# ProPrj_USB_Connector_2025-09-04.net
KiCad netlist of a schematic drawn in EasyEDA Pro
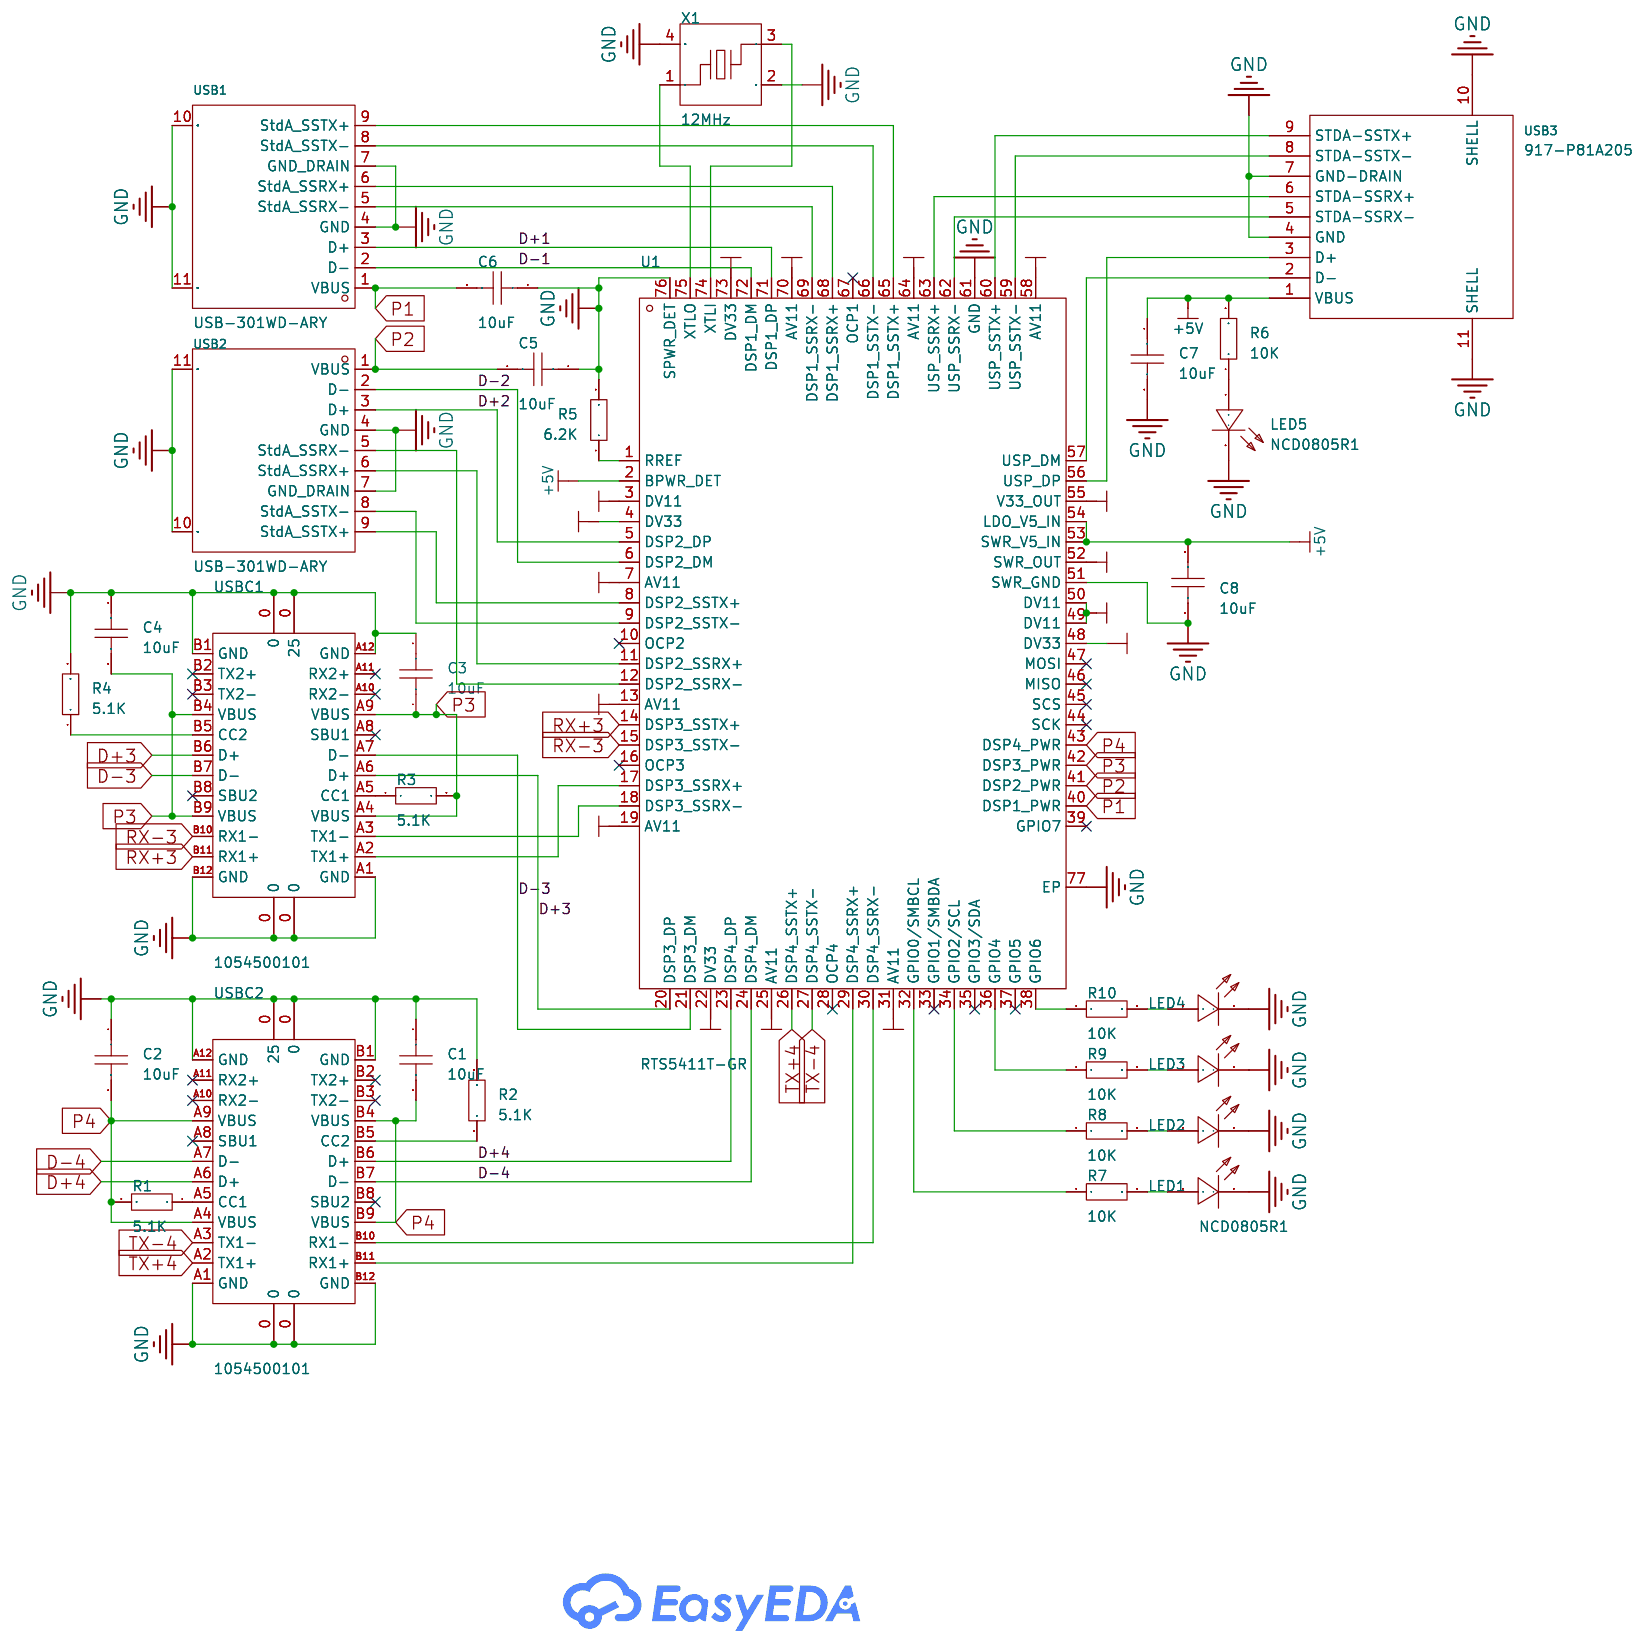
[diagram p0: schematic sheet]

(export (version "E")
  (design (tool "Eeschema 10.0.6"))
  (components
    (comp (ref "C1")
      (value "10uF")
      (footprint "easyedapro:C0603")
      (libsource (lib "easyedapro") (part "CAP"))
    )
    (comp (ref "C2")
      (value "10uF")
      (footprint "easyedapro:C0603")
      (libsource (lib "easyedapro") (part "CAP"))
    )
    (comp (ref "C3")
      (value "10uF")
      (footprint "easyedapro:C0603")
      (libsource (lib "easyedapro") (part "CAP"))
    )
    (comp (ref "C4")
      (value "10uF")
      (footprint "easyedapro:C0603")
      (libsource (lib "easyedapro") (part "CAP"))
    )
    (comp (ref "C5")
      (value "10uF")
      (footprint "easyedapro:C0603")
      (libsource (lib "easyedapro") (part "CAP"))
    )
    (comp (ref "C6")
      (value "10uF")
      (footprint "easyedapro:C0603")
      (libsource (lib "easyedapro") (part "CAP"))
    )
    (comp (ref "C7")
      (value "10uF")
      (footprint "easyedapro:C0603")
      (libsource (lib "easyedapro") (part "CAP"))
    )
    (comp (ref "C8")
      (value "10uF")
      (footprint "easyedapro:C0603")
      (libsource (lib "easyedapro") (part "CAP"))
    )
    (comp (ref "LED1")
      (value "NCD0805R1")
      (footprint "easyedapro:LED0805-R-RD")
      (fields (field (name "Manufacturer") "国星光电"))
      (libsource (lib "easyedapro") (part "FC-2012HRK-620D"))
    )
    (comp (ref "LED2")
      (value "NCD0805R1")
      (footprint "easyedapro:LED0805-R-RD")
      (fields (field (name "Manufacturer") "国星光电"))
      (libsource (lib "easyedapro") (part "FC-2012HRK-620D"))
    )
    (comp (ref "LED3")
      (value "NCD0805R1")
      (footprint "easyedapro:LED0805-R-RD")
      (fields (field (name "Manufacturer") "国星光电"))
      (libsource (lib "easyedapro") (part "FC-2012HRK-620D"))
    )
    (comp (ref "LED4")
      (value "NCD0805R1")
      (footprint "easyedapro:LED0805-R-RD")
      (fields (field (name "Manufacturer") "国星光电"))
      (libsource (lib "easyedapro") (part "FC-2012HRK-620D"))
    )
    (comp (ref "LED5")
      (value "NCD0805R1")
      (footprint "easyedapro:LED0805-R-RD")
      (fields (field (name "Manufacturer") "国星光电"))
      (libsource (lib "easyedapro") (part "FC-2012HRK-620D"))
    )
    (comp (ref "R1")
      (value "5.1K")
      (footprint "easyedapro:R0603")
      (libsource (lib "easyedapro") (part "Res"))
    )
    (comp (ref "R2")
      (value "5.1K")
      (footprint "easyedapro:R0603")
      (libsource (lib "easyedapro") (part "Res"))
    )
    (comp (ref "R3")
      (value "5.1K")
      (footprint "easyedapro:R0603")
      (libsource (lib "easyedapro") (part "Res"))
    )
    (comp (ref "R4")
      (value "5.1K")
      (footprint "easyedapro:R0603")
      (libsource (lib "easyedapro") (part "Res"))
    )
    (comp (ref "R5")
      (value "6.2K")
      (footprint "easyedapro:R0603")
      (libsource (lib "easyedapro") (part "Res"))
    )
    (comp (ref "R6") (value "10K") (footprint "easyedapro:R0603") (libsource (lib "easyedapro") (part "Res")))
    (comp (ref "R7") (value "10K") (footprint "easyedapro:R0603") (libsource (lib "easyedapro") (part "Res")))
    (comp (ref "R8") (value "10K") (footprint "easyedapro:R0603") (libsource (lib "easyedapro") (part "Res")))
    (comp (ref "R9") (value "10K") (footprint "easyedapro:R0603") (libsource (lib "easyedapro") (part "Res")))
    (comp (ref "R10")
      (value "10K")
      (footprint "easyedapro:R0603")
      (libsource (lib "easyedapro") (part "Res"))
    )
    (comp (ref "U1")
      (value "RTS5411T-GR")
      (footprint "easyedapro:QFN-76_L9.0-W9.0-P0.40-BL-EP5.4")
      (fields (field (name "Manufacturer") "REALTEK(瑞昱)"))
      (libsource (lib "easyedapro") (part "RTS5411T-GR"))
    )
    (comp (ref "USB1")
      (value "USB-301WD-ARY")
      (footprint "easyedapro:USB-TH_XUNPU_USB-301WD-ARY")
      (fields (field (name "Manufacturer") "XUNPU(讯普)"))
      (libsource (lib "easyedapro") (part "USB-301WD-ARY"))
    )
    (comp (ref "USB2")
      (value "USB-301WD-ARY")
      (footprint "easyedapro:USB-TH_XUNPU_USB-301WD-ARY")
      (fields (field (name "Manufacturer") "XUNPU(讯普)"))
      (libsource (lib "easyedapro") (part "USB-301WD-ARY"))
    )
    (comp (ref "USB3")
      (value "917-P81A205CS60202")
      (footprint "easyedapro:USB-3.0-SMD_CU3M002_USBA-M")
      (fields (field (name "Manufacturer") "精拓金"))
      (libsource (lib "easyedapro") (part "CU3M002_USB A/M 3.0 SMT L=1.9 K"))
    )
    (comp (ref "USBC1")
      (value "1054500101")
      (footprint "easyedapro:USB-C-SMD_TYPE-C-USB-18")
      (fields (field (name "Manufacturer") "MOLEX"))
      (libsource (lib "easyedapro") (part "105450-0101"))
    )
    (comp (ref "USBC2")
      (value "1054500101")
      (footprint "easyedapro:USB-C-SMD_TYPE-C-USB-18")
      (fields (field (name "Manufacturer") "MOLEX"))
      (libsource (lib "easyedapro") (part "105450-0101"))
    )
    (comp (ref "X1")
      (value "12MHz")
      (footprint "easyedapro:CRYSTAL-SMD_4P-L3.2-W2.5-BL-1")
      (fields
        (field (name "Manufacturer Part") "XL2EL89COI-111YLC-12M")
        (field (name "Manufacturer") "YXC(扬兴晶振)")
      )
      (libsource (lib "easyedapro") (part "XL2EL89COI-111YLC-12M"))
    )
  )
  (nets
    (net (code "1") (name "+1V1") (class "Default")
      (node (ref "U1") (pin "13") (pinfunction "AV11_13") (pintype "unspecified"))
      (node (ref "U1") (pin "19") (pinfunction "AV11_19") (pintype "unspecified"))
      (node (ref "U1") (pin "25") (pinfunction "AV11_25") (pintype "unspecified"))
      (node (ref "U1") (pin "3") (pinfunction "DV11_3") (pintype "unspecified"))
      (node (ref "U1") (pin "31") (pinfunction "AV11_31") (pintype "unspecified"))
      (node (ref "U1") (pin "49") (pinfunction "DV11_49") (pintype "unspecified"))
      (node (ref "U1") (pin "50") (pinfunction "DV11_50") (pintype "unspecified"))
      (node (ref "U1") (pin "52") (pinfunction "SWR_OUT_52") (pintype "unspecified"))
      (node (ref "U1") (pin "58") (pinfunction "AV11_58") (pintype "unspecified"))
      (node (ref "U1") (pin "64") (pinfunction "AV11_64") (pintype "unspecified"))
      (node (ref "U1") (pin "7") (pinfunction "AV11_7") (pintype "unspecified"))
      (node (ref "U1") (pin "70") (pinfunction "AV11_70") (pintype "unspecified"))
    )
    (net (code "2") (name "+3V3") (class "Default")
      (node (ref "U1") (pin "22") (pinfunction "DV33_22") (pintype "unspecified"))
      (node (ref "U1") (pin "4") (pinfunction "DV33_4") (pintype "unspecified"))
      (node (ref "U1") (pin "48") (pinfunction "DV33_48") (pintype "unspecified"))
      (node (ref "U1") (pin "55") (pinfunction "V33_OUT_55") (pintype "unspecified"))
      (node (ref "U1") (pin "73") (pinfunction "DV33_73") (pintype "unspecified"))
    )
    (net (code "3") (name "+5V") (class "Default")
      (node (ref "C7") (pin "1") (pinfunction "1_1") (pintype "input"))
      (node (ref "C8") (pin "2") (pinfunction "2_2") (pintype "input"))
      (node (ref "R6") (pin "2") (pinfunction "2_2") (pintype "input"))
      (node (ref "U1") (pin "2") (pinfunction "BPWR_DET_2") (pintype "unspecified"))
      (node (ref "U1") (pin "53") (pinfunction "SWR_V5_IN_53") (pintype "unspecified"))
      (node (ref "U1") (pin "54") (pinfunction "LDO_V5_IN_54") (pintype "unspecified"))
      (node (ref "USB3") (pin "1") (pinfunction "VBUS_1") (pintype "input"))
    )
    (net (code "4") (name "/D+1") (class "Default")
      (node (ref "U1") (pin "71") (pinfunction "DSP1_DP_71") (pintype "unspecified"))
      (node (ref "USB1") (pin "3") (pinfunction "D+_3") (pintype "input"))
    )
    (net (code "5") (name "/D+2") (class "Default")
      (node (ref "U1") (pin "5") (pinfunction "DSP2_DP_5") (pintype "unspecified"))
      (node (ref "USB2") (pin "3") (pinfunction "D+_3") (pintype "input"))
    )
    (net (code "6") (name "/D-1") (class "Default")
      (node (ref "U1") (pin "72") (pinfunction "DSP1_DM_72") (pintype "unspecified"))
      (node (ref "USB1") (pin "2") (pinfunction "D-_2") (pintype "input"))
    )
    (net (code "7") (name "/D-2") (class "Default")
      (node (ref "U1") (pin "6") (pinfunction "DSP2_DM_6") (pintype "unspecified"))
      (node (ref "USB2") (pin "2") (pinfunction "D-_2") (pintype "input"))
    )
    (net (code "8") (name "D+3") (class "Default")
      (node (ref "U1") (pin "20") (pinfunction "DSP3_DP_20") (pintype "unspecified"))
      (node (ref "USBC1") (pin "A6") (pinfunction "D+_A6") (pintype "unspecified"))
      (node (ref "USBC1") (pin "B6") (pinfunction "D+_B6") (pintype "unspecified"))
    )
    (net (code "9") (name "D+4") (class "Default")
      (node (ref "U1") (pin "23") (pinfunction "DSP4_DP_23") (pintype "unspecified"))
      (node (ref "USBC2") (pin "A6") (pinfunction "D+_A6") (pintype "unspecified"))
      (node (ref "USBC2") (pin "B6") (pinfunction "D+_B6") (pintype "unspecified"))
    )
    (net (code "10") (name "D-3") (class "Default")
      (node (ref "U1") (pin "21") (pinfunction "DSP3_DM_21") (pintype "unspecified"))
      (node (ref "USBC1") (pin "A7") (pinfunction "D-_A7") (pintype "unspecified"))
      (node (ref "USBC1") (pin "B7") (pinfunction "D-_B7") (pintype "unspecified"))
    )
    (net (code "11") (name "D-4") (class "Default")
      (node (ref "U1") (pin "24") (pinfunction "DSP4_DM_24") (pintype "unspecified"))
      (node (ref "USBC2") (pin "A7") (pinfunction "D-_A7") (pintype "unspecified"))
      (node (ref "USBC2") (pin "B7") (pinfunction "D-_B7") (pintype "unspecified"))
    )
    (net (code "12") (name "GND") (class "Default")
      (node (ref "C1") (pin "1") (pinfunction "1_1") (pintype "input"))
      (node (ref "C2") (pin "1") (pinfunction "1_1") (pintype "input"))
      (node (ref "C3") (pin "2") (pinfunction "2_2") (pintype "input"))
      (node (ref "C4") (pin "1") (pinfunction "1_1") (pintype "input"))
      (node (ref "C5") (pin "1") (pinfunction "1_1") (pintype "input"))
      (node (ref "C6") (pin "1") (pinfunction "1_1") (pintype "input"))
      (node (ref "C7") (pin "2") (pinfunction "2_2") (pintype "input"))
      (node (ref "C8") (pin "1") (pinfunction "1_1") (pintype "input"))
      (node (ref "LED1") (pin "2") (pinfunction "-_2") (pintype "unspecified"))
      (node (ref "LED2") (pin "2") (pinfunction "-_2") (pintype "unspecified"))
      (node (ref "LED3") (pin "2") (pinfunction "-_2") (pintype "unspecified"))
      (node (ref "LED4") (pin "2") (pinfunction "-_2") (pintype "unspecified"))
      (node (ref "LED5") (pin "2") (pinfunction "-_2") (pintype "unspecified"))
      (node (ref "R2") (pin "2") (pinfunction "2_2") (pintype "input"))
      (node (ref "R4") (pin "2") (pinfunction "2_2") (pintype "input"))
      (node (ref "R5") (pin "2") (pinfunction "2_2") (pintype "input"))
      (node (ref "U1") (pin "51") (pinfunction "SWR_GND_51") (pintype "unspecified"))
      (node (ref "U1") (pin "61") (pinfunction "GND_61") (pintype "unspecified"))
      (node (ref "U1") (pin "76") (pinfunction "SPWR_DET_76") (pintype "unspecified"))
      (node (ref "U1") (pin "77") (pinfunction "EP_77") (pintype "unspecified"))
      (node (ref "USB1") (pin "10") (pinfunction "SHIELD_10") (pintype "input"))
      (node (ref "USB1") (pin "11") (pinfunction "SHIELD_11") (pintype "input"))
      (node (ref "USB1") (pin "4") (pinfunction "GND_4") (pintype "input"))
      (node (ref "USB1") (pin "7") (pinfunction "GND_DRAIN_7") (pintype "input"))
      (node (ref "USB2") (pin "10") (pinfunction "SHIELD_10") (pintype "input"))
      (node (ref "USB2") (pin "11") (pinfunction "SHIELD_11") (pintype "input"))
      (node (ref "USB2") (pin "4") (pinfunction "GND_4") (pintype "input"))
      (node (ref "USB2") (pin "7") (pinfunction "GND_DRAIN_7") (pintype "input"))
      (node (ref "USB3") (pin "10") (pinfunction "SHELL_10") (pintype "input"))
      (node (ref "USB3") (pin "11") (pinfunction "SHELL_11") (pintype "input"))
      (node (ref "USB3") (pin "4") (pinfunction "GND_4") (pintype "input"))
      (node (ref "USB3") (pin "7") (pinfunction "GND-DRAIN_7") (pintype "input"))
      (node (ref "USBC1") (pin "0") (pinfunction "0_0") (pintype "unspecified"))
      (node (ref "USBC1") (pin "A1") (pinfunction "GND_A1") (pintype "unspecified"))
      (node (ref "USBC1") (pin "A12") (pinfunction "GND_A12") (pintype "unspecified"))
      (node (ref "USBC1") (pin "B1") (pinfunction "GND_B1") (pintype "unspecified"))
      (node (ref "USBC1") (pin "B12") (pinfunction "GND_B12") (pintype "unspecified"))
      (node (ref "USBC2") (pin "0") (pinfunction "25_0") (pintype "unspecified"))
      (node (ref "USBC2") (pin "A1") (pinfunction "GND_A1") (pintype "unspecified"))
      (node (ref "USBC2") (pin "A12") (pinfunction "GND_A12") (pintype "unspecified"))
      (node (ref "USBC2") (pin "B1") (pinfunction "GND_B1") (pintype "unspecified"))
      (node (ref "USBC2") (pin "B12") (pinfunction "GND_B12") (pintype "unspecified"))
      (node (ref "X1") (pin "2") (pinfunction "GND_2") (pintype "input"))
      (node (ref "X1") (pin "4") (pinfunction "GND_4") (pintype "input"))
    )
    (net (code "13") (name "Net-(LED1-+)") (class "Default")
      (node (ref "LED1") (pin "1") (pinfunction "+_1") (pintype "unspecified"))
      (node (ref "R7") (pin "2") (pinfunction "2_2") (pintype "input"))
    )
    (net (code "14") (name "Net-(LED2-+)") (class "Default")
      (node (ref "LED2") (pin "1") (pinfunction "+_1") (pintype "unspecified"))
      (node (ref "R8") (pin "2") (pinfunction "2_2") (pintype "input"))
    )
    (net (code "15") (name "Net-(LED3-+)") (class "Default")
      (node (ref "LED3") (pin "1") (pinfunction "+_1") (pintype "unspecified"))
      (node (ref "R9") (pin "2") (pinfunction "2_2") (pintype "input"))
    )
    (net (code "16") (name "Net-(LED4-+)") (class "Default")
      (node (ref "LED4") (pin "1") (pinfunction "+_1") (pintype "unspecified"))
      (node (ref "R10") (pin "2") (pinfunction "2_2") (pintype "input"))
    )
    (net (code "17") (name "Net-(LED5-+)") (class "Default")
      (node (ref "LED5") (pin "1") (pinfunction "+_1") (pintype "unspecified"))
      (node (ref "R6") (pin "1") (pinfunction "1_1") (pintype "input"))
    )
    (net (code "18") (name "Net-(U1-DSP1_SSRX+)") (class "Default")
      (node (ref "U1") (pin "68") (pinfunction "DSP1_SSRX+_68") (pintype "unspecified"))
      (node (ref "USB1") (pin "6") (pinfunction "StdA_SSRX+_6") (pintype "input"))
    )
    (net (code "19") (name "Net-(U1-DSP1_SSRX-)") (class "Default")
      (node (ref "U1") (pin "69") (pinfunction "DSP1_SSRX-_69") (pintype "unspecified"))
      (node (ref "USB1") (pin "5") (pinfunction "StdA_SSRX-_5") (pintype "input"))
    )
    (net (code "20") (name "Net-(U1-DSP1_SSTX+)") (class "Default")
      (node (ref "U1") (pin "65") (pinfunction "DSP1_SSTX+_65") (pintype "unspecified"))
      (node (ref "USB1") (pin "9") (pinfunction "StdA_SSTX+_9") (pintype "input"))
    )
    (net (code "21") (name "Net-(U1-DSP1_SSTX-)") (class "Default")
      (node (ref "U1") (pin "66") (pinfunction "DSP1_SSTX-_66") (pintype "unspecified"))
      (node (ref "USB1") (pin "8") (pinfunction "StdA_SSTX-_8") (pintype "input"))
    )
    (net (code "22") (name "Net-(U1-DSP2_SSRX+)") (class "Default")
      (node (ref "U1") (pin "11") (pinfunction "DSP2_SSRX+_11") (pintype "unspecified"))
      (node (ref "USB2") (pin "6") (pinfunction "StdA_SSRX+_6") (pintype "input"))
    )
    (net (code "23") (name "Net-(U1-DSP2_SSRX-)") (class "Default")
      (node (ref "U1") (pin "12") (pinfunction "DSP2_SSRX-_12") (pintype "unspecified"))
      (node (ref "USB2") (pin "5") (pinfunction "StdA_SSRX-_5") (pintype "input"))
    )
    (net (code "24") (name "Net-(U1-DSP2_SSTX+)") (class "Default")
      (node (ref "U1") (pin "8") (pinfunction "DSP2_SSTX+_8") (pintype "unspecified"))
      (node (ref "USB2") (pin "9") (pinfunction "StdA_SSTX+_9") (pintype "input"))
    )
    (net (code "25") (name "Net-(U1-DSP2_SSTX-)") (class "Default")
      (node (ref "U1") (pin "9") (pinfunction "DSP2_SSTX-_9") (pintype "unspecified"))
      (node (ref "USB2") (pin "8") (pinfunction "StdA_SSTX-_8") (pintype "input"))
    )
    (net (code "26") (name "Net-(U1-DSP3_SSRX+)") (class "Default")
      (node (ref "U1") (pin "17") (pinfunction "DSP3_SSRX+_17") (pintype "unspecified"))
      (node (ref "USBC1") (pin "A2") (pinfunction "TX1+_A2") (pintype "unspecified"))
    )
    (net (code "27") (name "Net-(U1-DSP3_SSRX-)") (class "Default")
      (node (ref "U1") (pin "18") (pinfunction "DSP3_SSRX-_18") (pintype "unspecified"))
      (node (ref "USBC1") (pin "A3") (pinfunction "TX1-_A3") (pintype "unspecified"))
    )
    (net (code "28") (name "Net-(U1-DSP4_SSRX+)") (class "Default")
      (node (ref "U1") (pin "29") (pinfunction "DSP4_SSRX+_29") (pintype "unspecified"))
      (node (ref "USBC2") (pin "B11") (pinfunction "RX1+_B11") (pintype "unspecified"))
    )
    (net (code "29") (name "Net-(U1-DSP4_SSRX-)") (class "Default")
      (node (ref "U1") (pin "30") (pinfunction "DSP4_SSRX-_30") (pintype "unspecified"))
      (node (ref "USBC2") (pin "B10") (pinfunction "RX1-_B10") (pintype "unspecified"))
    )
    (net (code "30") (name "Net-(U1-GPIO0{slash}SMBCL)") (class "Default")
      (node (ref "R7") (pin "1") (pinfunction "1_1") (pintype "input"))
      (node (ref "U1") (pin "32") (pinfunction "GPIO0/SMBCL_32") (pintype "unspecified"))
    )
    (net (code "31") (name "Net-(U1-GPIO2{slash}SCL)") (class "Default")
      (node (ref "R8") (pin "1") (pinfunction "1_1") (pintype "input"))
      (node (ref "U1") (pin "34") (pinfunction "GPIO2/SCL_34") (pintype "unspecified"))
    )
    (net (code "32") (name "Net-(U1-GPIO4)") (class "Default")
      (node (ref "R9") (pin "1") (pinfunction "1_1") (pintype "input"))
      (node (ref "U1") (pin "36") (pinfunction "GPIO4_36") (pintype "unspecified"))
    )
    (net (code "33") (name "Net-(U1-GPIO6)") (class "Default")
      (node (ref "R10") (pin "1") (pinfunction "1_1") (pintype "input"))
      (node (ref "U1") (pin "38") (pinfunction "GPIO6_38") (pintype "unspecified"))
    )
    (net (code "34") (name "Net-(U1-RREF)") (class "Default")
      (node (ref "R5") (pin "1") (pinfunction "1_1") (pintype "input"))
      (node (ref "U1") (pin "1") (pinfunction "RREF_1") (pintype "unspecified"))
    )
    (net (code "35") (name "Net-(U1-USP_DM)") (class "Default")
      (node (ref "U1") (pin "57") (pinfunction "USP_DM_57") (pintype "unspecified"))
      (node (ref "USB3") (pin "2") (pinfunction "D-_2") (pintype "input"))
    )
    (net (code "36") (name "Net-(U1-USP_DP)") (class "Default")
      (node (ref "U1") (pin "56") (pinfunction "USP_DP_56") (pintype "unspecified"))
      (node (ref "USB3") (pin "3") (pinfunction "D+_3") (pintype "input"))
    )
    (net (code "37") (name "Net-(U1-USP_SSRX+)") (class "Default")
      (node (ref "U1") (pin "63") (pinfunction "USP_SSRX+_63") (pintype "unspecified"))
      (node (ref "USB3") (pin "6") (pinfunction "STDA-SSRX+_6") (pintype "input"))
    )
    (net (code "38") (name "Net-(U1-USP_SSRX-)") (class "Default")
      (node (ref "U1") (pin "62") (pinfunction "USP_SSRX-_62") (pintype "unspecified"))
      (node (ref "USB3") (pin "5") (pinfunction "STDA-SSRX-_5") (pintype "input"))
    )
    (net (code "39") (name "Net-(U1-USP_SSTX+)") (class "Default")
      (node (ref "U1") (pin "60") (pinfunction "USP_SSTX+_60") (pintype "unspecified"))
      (node (ref "USB3") (pin "9") (pinfunction "STDA-SSTX+_9") (pintype "input"))
    )
    (net (code "40") (name "Net-(U1-USP_SSTX-)") (class "Default")
      (node (ref "U1") (pin "59") (pinfunction "USP_SSTX-_59") (pintype "unspecified"))
      (node (ref "USB3") (pin "8") (pinfunction "STDA-SSTX-_8") (pintype "input"))
    )
    (net (code "41") (name "Net-(U1-XTLI)") (class "Default")
      (node (ref "U1") (pin "74") (pinfunction "XTLI_74") (pintype "unspecified"))
      (node (ref "X1") (pin "3") (pinfunction "3_3") (pintype "input"))
    )
    (net (code "42") (name "Net-(U1-XTLO)") (class "Default")
      (node (ref "U1") (pin "75") (pinfunction "XTLO_75") (pintype "unspecified"))
      (node (ref "X1") (pin "1") (pinfunction "1_1") (pintype "input"))
    )
    (net (code "43") (name "Net-(USBC1-CC1)") (class "Default")
      (node (ref "R3") (pin "1") (pinfunction "1_1") (pintype "input"))
      (node (ref "USBC1") (pin "A5") (pinfunction "CC1_A5") (pintype "unspecified"))
    )
    (net (code "44") (name "Net-(USBC1-CC2)") (class "Default")
      (node (ref "R4") (pin "1") (pinfunction "1_1") (pintype "input"))
      (node (ref "USBC1") (pin "B5") (pinfunction "CC2_B5") (pintype "unspecified"))
    )
    (net (code "45") (name "Net-(USBC2-CC1)") (class "Default")
      (node (ref "R1") (pin "1") (pinfunction "1_1") (pintype "input"))
      (node (ref "USBC2") (pin "A5") (pinfunction "CC1_A5") (pintype "unspecified"))
    )
    (net (code "46") (name "Net-(USBC2-CC2)") (class "Default")
      (node (ref "R2") (pin "1") (pinfunction "1_1") (pintype "input"))
      (node (ref "USBC2") (pin "B5") (pinfunction "CC2_B5") (pintype "unspecified"))
    )
    (net (code "47") (name "P1") (class "Default")
      (node (ref "C6") (pin "2") (pinfunction "2_2") (pintype "input"))
      (node (ref "U1") (pin "40") (pinfunction "DSP1_PWR_40") (pintype "unspecified"))
      (node (ref "USB1") (pin "1") (pinfunction "VBUS_1") (pintype "input"))
    )
    (net (code "48") (name "P2") (class "Default")
      (node (ref "C5") (pin "2") (pinfunction "2_2") (pintype "input"))
      (node (ref "U1") (pin "41") (pinfunction "DSP2_PWR_41") (pintype "unspecified"))
      (node (ref "USB2") (pin "1") (pinfunction "VBUS_1") (pintype "input"))
    )
    (net (code "49") (name "P3") (class "Default")
      (node (ref "C3") (pin "1") (pinfunction "1_1") (pintype "input"))
      (node (ref "C4") (pin "2") (pinfunction "2_2") (pintype "input"))
      (node (ref "R3") (pin "2") (pinfunction "2_2") (pintype "input"))
      (node (ref "U1") (pin "42") (pinfunction "DSP3_PWR_42") (pintype "unspecified"))
      (node (ref "USBC1") (pin "A4") (pinfunction "VBUS_A4") (pintype "unspecified"))
      (node (ref "USBC1") (pin "A9") (pinfunction "VBUS_A9") (pintype "unspecified"))
      (node (ref "USBC1") (pin "B4") (pinfunction "VBUS_B4") (pintype "unspecified"))
      (node (ref "USBC1") (pin "B9") (pinfunction "VBUS_B9") (pintype "unspecified"))
    )
    (net (code "50") (name "P4") (class "Default")
      (node (ref "C1") (pin "2") (pinfunction "2_2") (pintype "input"))
      (node (ref "C2") (pin "2") (pinfunction "2_2") (pintype "input"))
      (node (ref "R1") (pin "2") (pinfunction "2_2") (pintype "input"))
      (node (ref "U1") (pin "43") (pinfunction "DSP4_PWR_43") (pintype "unspecified"))
      (node (ref "USBC2") (pin "A4") (pinfunction "VBUS_A4") (pintype "unspecified"))
      (node (ref "USBC2") (pin "A9") (pinfunction "VBUS_A9") (pintype "unspecified"))
      (node (ref "USBC2") (pin "B4") (pinfunction "VBUS_B4") (pintype "unspecified"))
      (node (ref "USBC2") (pin "B9") (pinfunction "VBUS_B9") (pintype "unspecified"))
    )
    (net (code "51") (name "RX+3") (class "Default")
      (node (ref "U1") (pin "14") (pinfunction "DSP3_SSTX+_14") (pintype "unspecified"))
      (node (ref "USBC1") (pin "B11") (pinfunction "RX1+_B11") (pintype "unspecified"))
    )
    (net (code "52") (name "RX-3") (class "Default")
      (node (ref "U1") (pin "15") (pinfunction "DSP3_SSTX-_15") (pintype "unspecified"))
      (node (ref "USBC1") (pin "B10") (pinfunction "RX1-_B10") (pintype "unspecified"))
    )
    (net (code "53") (name "TX+4") (class "Default")
      (node (ref "U1") (pin "26") (pinfunction "DSP4_SSTX+_26") (pintype "unspecified"))
      (node (ref "USBC2") (pin "A2") (pinfunction "TX1+_A2") (pintype "unspecified"))
    )
    (net (code "54") (name "TX-4") (class "Default")
      (node (ref "U1") (pin "27") (pinfunction "DSP4_SSTX-_27") (pintype "unspecified"))
      (node (ref "USBC2") (pin "A3") (pinfunction "TX1-_A3") (pintype "unspecified"))
    )
    (net (code "55") (name "unconnected-(U1-GPIO1{slash}SMBDA-Pad33)") (class "Default")
      (node (ref "U1") (pin "33") (pinfunction "GPIO1/SMBDA_33") (pintype "unspecified+no_connect"))
    )
    (net (code "56") (name "unconnected-(U1-GPIO3{slash}SDA-Pad35)") (class "Default")
      (node (ref "U1") (pin "35") (pinfunction "GPIO3/SDA_35") (pintype "unspecified+no_connect"))
    )
    (net (code "57") (name "unconnected-(U1-GPIO5-Pad37)") (class "Default")
      (node (ref "U1") (pin "37") (pinfunction "GPIO5_37") (pintype "unspecified+no_connect"))
    )
    (net (code "58") (name "unconnected-(U1-GPIO7-Pad39)") (class "Default")
      (node (ref "U1") (pin "39") (pinfunction "GPIO7_39") (pintype "unspecified+no_connect"))
    )
    (net (code "59") (name "unconnected-(U1-MISO-Pad46)") (class "Default")
      (node (ref "U1") (pin "46") (pinfunction "MISO_46") (pintype "unspecified+no_connect"))
    )
    (net (code "60") (name "unconnected-(U1-MOSI-Pad47)") (class "Default")
      (node (ref "U1") (pin "47") (pinfunction "MOSI_47") (pintype "unspecified+no_connect"))
    )
    (net (code "61") (name "unconnected-(U1-OCP1-Pad67)") (class "Default")
      (node (ref "U1") (pin "67") (pinfunction "OCP1_67") (pintype "unspecified+no_connect"))
    )
    (net (code "62") (name "unconnected-(U1-OCP2-Pad10)") (class "Default")
      (node (ref "U1") (pin "10") (pinfunction "OCP2_10") (pintype "unspecified+no_connect"))
    )
    (net (code "63") (name "unconnected-(U1-OCP3-Pad16)") (class "Default")
      (node (ref "U1") (pin "16") (pinfunction "OCP3_16") (pintype "unspecified+no_connect"))
    )
    (net (code "64") (name "unconnected-(U1-OCP4-Pad28)") (class "Default")
      (node (ref "U1") (pin "28") (pinfunction "OCP4_28") (pintype "unspecified+no_connect"))
    )
    (net (code "65") (name "unconnected-(U1-SCK-Pad44)") (class "Default")
      (node (ref "U1") (pin "44") (pinfunction "SCK_44") (pintype "unspecified+no_connect"))
    )
    (net (code "66") (name "unconnected-(U1-SCS-Pad45)") (class "Default")
      (node (ref "U1") (pin "45") (pinfunction "SCS_45") (pintype "unspecified+no_connect"))
    )
    (net (code "67") (name "unconnected-(USBC1-RX2+-PadA11)") (class "Default")
      (node (ref "USBC1") (pin "A11") (pinfunction "RX2+_A11") (pintype "unspecified+no_connect"))
    )
    (net (code "68") (name "unconnected-(USBC1-RX2--PadA10)") (class "Default")
      (node (ref "USBC1") (pin "A10") (pinfunction "RX2-_A10") (pintype "unspecified+no_connect"))
    )
    (net (code "69") (name "unconnected-(USBC1-SBU1-PadA8)") (class "Default")
      (node (ref "USBC1") (pin "A8") (pinfunction "SBU1_A8") (pintype "unspecified+no_connect"))
    )
    (net (code "70") (name "unconnected-(USBC1-SBU2-PadB8)") (class "Default")
      (node (ref "USBC1") (pin "B8") (pinfunction "SBU2_B8") (pintype "unspecified+no_connect"))
    )
    (net (code "71") (name "unconnected-(USBC1-TX2+-PadB2)") (class "Default")
      (node (ref "USBC1") (pin "B2") (pinfunction "TX2+_B2") (pintype "unspecified+no_connect"))
    )
    (net (code "72") (name "unconnected-(USBC1-TX2--PadB3)") (class "Default")
      (node (ref "USBC1") (pin "B3") (pinfunction "TX2-_B3") (pintype "unspecified+no_connect"))
    )
    (net (code "73") (name "unconnected-(USBC2-RX2+-PadA11)") (class "Default")
      (node (ref "USBC2") (pin "A11") (pinfunction "RX2+_A11") (pintype "unspecified+no_connect"))
    )
    (net (code "74") (name "unconnected-(USBC2-RX2--PadA10)") (class "Default")
      (node (ref "USBC2") (pin "A10") (pinfunction "RX2-_A10") (pintype "unspecified+no_connect"))
    )
    (net (code "75") (name "unconnected-(USBC2-SBU1-PadA8)") (class "Default")
      (node (ref "USBC2") (pin "A8") (pinfunction "SBU1_A8") (pintype "unspecified+no_connect"))
    )
    (net (code "76") (name "unconnected-(USBC2-SBU2-PadB8)") (class "Default")
      (node (ref "USBC2") (pin "B8") (pinfunction "SBU2_B8") (pintype "unspecified+no_connect"))
    )
    (net (code "77") (name "unconnected-(USBC2-TX2+-PadB2)") (class "Default")
      (node (ref "USBC2") (pin "B2") (pinfunction "TX2+_B2") (pintype "unspecified+no_connect"))
    )
    (net (code "78") (name "unconnected-(USBC2-TX2--PadB3)") (class "Default")
      (node (ref "USBC2") (pin "B3") (pinfunction "TX2-_B3") (pintype "unspecified+no_connect"))
    )
  )
)
